# USB_SMBus.net
KiCad netlist of a schematic drawn in EAGLE
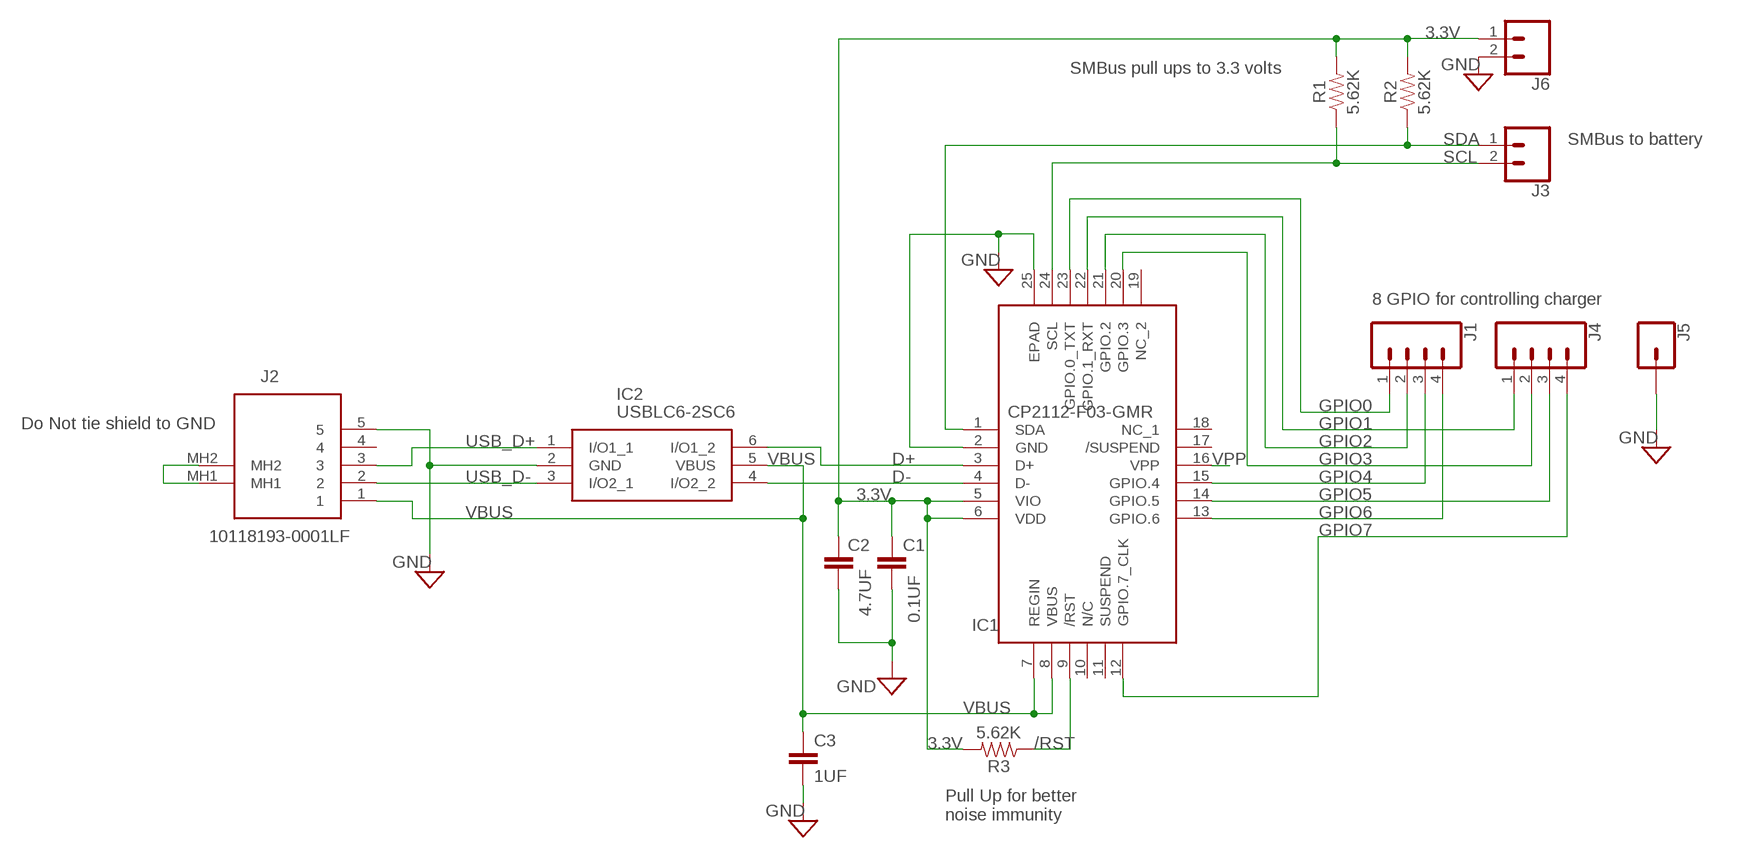
[diagram p0: schematic, sheet 1]

(export (version "E")
  (design (tool "Eeschema 10.0.6"))
  (components
    (comp (ref "C1")
      (value "0.1UF")
      (footprint "eagle-import:0805_CAP")
      (libsource (lib "eagle-import") (part "0805_CAP"))
    )
    (comp (ref "C2")
      (value "4.7UF")
      (footprint "eagle-import:0805_CAP")
      (libsource (lib "eagle-import") (part "0805_CAP"))
    )
    (comp (ref "C3")
      (value "1UF")
      (footprint "eagle-import:0805_CAP")
      (libsource (lib "eagle-import") (part "0805_CAP"))
    )
    (comp (ref "IC1")
      (value "CP2112-F03-GMR")
      (footprint "eagle-import:QFN50P400X400X80-25N")
      (fields (field (name "MOUSER_PART_NUMBER") "634-CP2112-F03-GMR"))
      (libsource (lib "eagle-import") (part "CP2112-F03-GMR"))
    )
    (comp (ref "IC2")
      (value "USBLC6-2SC6")
      (footprint "eagle-import:SOT95P280X145-6N")
      (fields (field (name "MOUSER_PART_NUMBER") "511-USBLC6-2SC6"))
      (libsource (lib "eagle-import") (part "USBLC6-2SC6"))
    )
    (comp (ref "J1")
      (value "CONN_04")
      (footprint "eagle-import:1X04")
      (libsource (lib "eagle-import") (part "CONN_04"))
    )
    (comp (ref "J2")
      (value "10118193-0001LF")
      (footprint "eagle-import:101181930001LF")
      (fields (field (name "MOUSER_PART_NUMBER") "649-10118193-0001LF"))
      (libsource (lib "eagle-import") (part "10118193-0001LF"))
    )
    (comp (ref "J3")
      (value "CONN_02")
      (footprint "eagle-import:1X02")
      (libsource (lib "eagle-import") (part "CONN_02"))
    )
    (comp (ref "J4")
      (value "CONN_04")
      (footprint "eagle-import:1X04")
      (libsource (lib "eagle-import") (part "CONN_04"))
    )
    (comp (ref "J5")
      (value "CONN_01")
      (footprint "eagle-import:1X01")
      (libsource (lib "eagle-import") (part "CONN_01"))
    )
    (comp (ref "J6")
      (value "CONN_02")
      (footprint "eagle-import:1X02")
      (libsource (lib "eagle-import") (part "CONN_02"))
    )
    (comp (ref "R1")
      (value "5.62K")
      (footprint "eagle-import:0603_RESISTOR")
      (libsource (lib "eagle-import") (part "0603_RESISTOR"))
    )
    (comp (ref "R2")
      (value "5.62K")
      (footprint "eagle-import:0603_RESISTOR")
      (libsource (lib "eagle-import") (part "0603_RESISTOR"))
    )
    (comp (ref "R3")
      (value "5.62K")
      (footprint "eagle-import:0603_RESISTOR")
      (libsource (lib "eagle-import") (part "0603_RESISTOR"))
    )
  )
  (nets
    (net (code "1") (name "/3.3V") (class "Default")
      (node (ref "C1") (pin "1") (pinfunction "1_1") (pintype "passive"))
      (node (ref "C2") (pin "1") (pinfunction "1_1") (pintype "passive"))
      (node (ref "IC1") (pin "5") (pinfunction "VIO_5") (pintype "bidirectional"))
      (node (ref "IC1") (pin "6") (pinfunction "VDD_6") (pintype "bidirectional"))
      (node (ref "J6") (pin "1") (pinfunction "1_1") (pintype "passive"))
      (node (ref "R1") (pin "2") (pinfunction "2_2") (pintype "passive"))
      (node (ref "R2") (pin "2") (pinfunction "2_2") (pintype "passive"))
      (node (ref "R3") (pin "2") (pinfunction "2_2") (pintype "passive"))
    )
    (net (code "2") (name "/D+") (class "Default")
      (node (ref "IC1") (pin "3") (pinfunction "D+_3") (pintype "bidirectional"))
      (node (ref "IC2") (pin "6") (pinfunction "I/O1_2_6") (pintype "bidirectional"))
    )
    (net (code "3") (name "/D-") (class "Default")
      (node (ref "IC1") (pin "4") (pinfunction "D-_4") (pintype "bidirectional"))
      (node (ref "IC2") (pin "4") (pinfunction "I/O2_2_4") (pintype "bidirectional"))
    )
    (net (code "4") (name "/GPIO0") (class "Default")
      (node (ref "IC1") (pin "23") (pinfunction "GPIO.0_TXT_23") (pintype "bidirectional"))
      (node (ref "J1") (pin "1") (pinfunction "1_1") (pintype "passive"))
    )
    (net (code "5") (name "/GPIO1") (class "Default")
      (node (ref "IC1") (pin "22") (pinfunction "GPIO.1_RXT_22") (pintype "bidirectional"))
      (node (ref "J4") (pin "1") (pinfunction "1_1") (pintype "passive"))
    )
    (net (code "6") (name "/GPIO2") (class "Default")
      (node (ref "IC1") (pin "21") (pinfunction "GPIO.2_21") (pintype "bidirectional"))
      (node (ref "J1") (pin "2") (pinfunction "2_2") (pintype "passive"))
    )
    (net (code "7") (name "/GPIO3") (class "Default")
      (node (ref "IC1") (pin "20") (pinfunction "GPIO.3_20") (pintype "bidirectional"))
      (node (ref "J4") (pin "2") (pinfunction "2_2") (pintype "passive"))
    )
    (net (code "8") (name "/GPIO4") (class "Default")
      (node (ref "IC1") (pin "15") (pinfunction "GPIO.4_15") (pintype "bidirectional"))
      (node (ref "J1") (pin "3") (pinfunction "3_3") (pintype "passive"))
    )
    (net (code "9") (name "/GPIO5") (class "Default")
      (node (ref "IC1") (pin "14") (pinfunction "GPIO.5_14") (pintype "bidirectional"))
      (node (ref "J4") (pin "3") (pinfunction "3_3") (pintype "passive"))
    )
    (net (code "10") (name "/GPIO6") (class "Default")
      (node (ref "IC1") (pin "13") (pinfunction "GPIO.6_13") (pintype "bidirectional"))
      (node (ref "J1") (pin "4") (pinfunction "4_4") (pintype "passive"))
    )
    (net (code "11") (name "/GPIO7") (class "Default")
      (node (ref "IC1") (pin "12") (pinfunction "GPIO.7_CLK_12") (pintype "bidirectional"))
      (node (ref "J4") (pin "4") (pinfunction "4_4") (pintype "passive"))
    )
    (net (code "12") (name "/SCL") (class "Default")
      (node (ref "IC1") (pin "24") (pinfunction "SCL_24") (pintype "bidirectional"))
      (node (ref "J3") (pin "2") (pinfunction "2_2") (pintype "passive"))
      (node (ref "R1") (pin "1") (pinfunction "1_1") (pintype "passive"))
    )
    (net (code "13") (name "/SDA") (class "Default")
      (node (ref "IC1") (pin "1") (pinfunction "SDA_1") (pintype "bidirectional"))
      (node (ref "J3") (pin "1") (pinfunction "1_1") (pintype "passive"))
      (node (ref "R2") (pin "1") (pinfunction "1_1") (pintype "passive"))
    )
    (net (code "14") (name "/USB_D+") (class "Default")
      (node (ref "IC2") (pin "1") (pinfunction "I/O1_1_1") (pintype "bidirectional"))
      (node (ref "J2") (pin "3") (pinfunction "3_3") (pintype "bidirectional"))
    )
    (net (code "15") (name "/USB_D-") (class "Default")
      (node (ref "IC2") (pin "3") (pinfunction "I/O2_1_3") (pintype "bidirectional"))
      (node (ref "J2") (pin "2") (pinfunction "2_2") (pintype "bidirectional"))
    )
    (net (code "16") (name "/VBUS") (class "Default")
      (node (ref "C3") (pin "1") (pinfunction "1_1") (pintype "passive"))
      (node (ref "IC1") (pin "7") (pinfunction "REGIN_7") (pintype "bidirectional"))
      (node (ref "IC1") (pin "8") (pinfunction "VBUS_8") (pintype "bidirectional"))
      (node (ref "IC2") (pin "5") (pinfunction "VBUS_5") (pintype "bidirectional"))
      (node (ref "J2") (pin "1") (pinfunction "1_1") (pintype "bidirectional"))
    )
    (net (code "17") (name "/VPP") (class "Default")
      (node (ref "IC1") (pin "16") (pinfunction "VPP_16") (pintype "bidirectional"))
    )
    (net (code "18") (name "/{slash}RST") (class "Default")
      (node (ref "IC1") (pin "9") (pinfunction "/RST_9") (pintype "bidirectional"))
      (node (ref "R3") (pin "1") (pinfunction "1_1") (pintype "passive"))
    )
    (net (code "19") (name "GND") (class "Default")
      (node (ref "C1") (pin "2") (pinfunction "2_2") (pintype "passive"))
      (node (ref "C2") (pin "2") (pinfunction "2_2") (pintype "passive"))
      (node (ref "C3") (pin "2") (pinfunction "2_2") (pintype "passive"))
      (node (ref "IC1") (pin "2") (pinfunction "GND_2") (pintype "bidirectional"))
      (node (ref "IC1") (pin "25") (pinfunction "EPAD_25") (pintype "bidirectional"))
      (node (ref "IC2") (pin "2") (pinfunction "GND_2") (pintype "bidirectional"))
      (node (ref "J2") (pin "5") (pinfunction "5_5") (pintype "bidirectional"))
      (node (ref "J5") (pin "1") (pinfunction "1_1") (pintype "passive"))
      (node (ref "J6") (pin "2") (pinfunction "2_2") (pintype "passive"))
    )
    (net (code "20") (name "Net-(J2-PadMH1)") (class "Default")
      (node (ref "J2") (pin "MH1") (pinfunction "MH1_MH1") (pintype "bidirectional"))
      (node (ref "J2") (pin "MH2") (pinfunction "MH2_MH2") (pintype "bidirectional"))
    )
    (net (code "21") (name "unconnected-(IC1-NC_1-Pad18)") (class "Default")
      (node (ref "IC1") (pin "18") (pinfunction "NC_1_18") (pintype "bidirectional"))
    )
    (net (code "22") (name "unconnected-(IC1-NC_2-Pad19)") (class "Default")
      (node (ref "IC1") (pin "19") (pinfunction "NC_2_19") (pintype "bidirectional"))
    )
    (net (code "23") (name "unconnected-(IC1-N{slash}C-Pad10)") (class "Default")
      (node (ref "IC1") (pin "10") (pinfunction "N/C_10") (pintype "no_connect"))
    )
    (net (code "24") (name "unconnected-(IC1-SUSPEND-Pad11)") (class "Default")
      (node (ref "IC1") (pin "11") (pinfunction "SUSPEND_11") (pintype "bidirectional"))
    )
    (net (code "25") (name "unconnected-(IC1-{slash}SUSPEND-Pad17)") (class "Default")
      (node (ref "IC1") (pin "17") (pinfunction "/SUSPEND_17") (pintype "bidirectional"))
    )
    (net (code "26") (name "unconnected-(J2-Pad4)") (class "Default")
      (node (ref "J2") (pin "4") (pinfunction "4_4") (pintype "bidirectional"))
    )
  )
)
